# Sheet1.net
KiCad netlist of a schematic drawn in Altium Designer
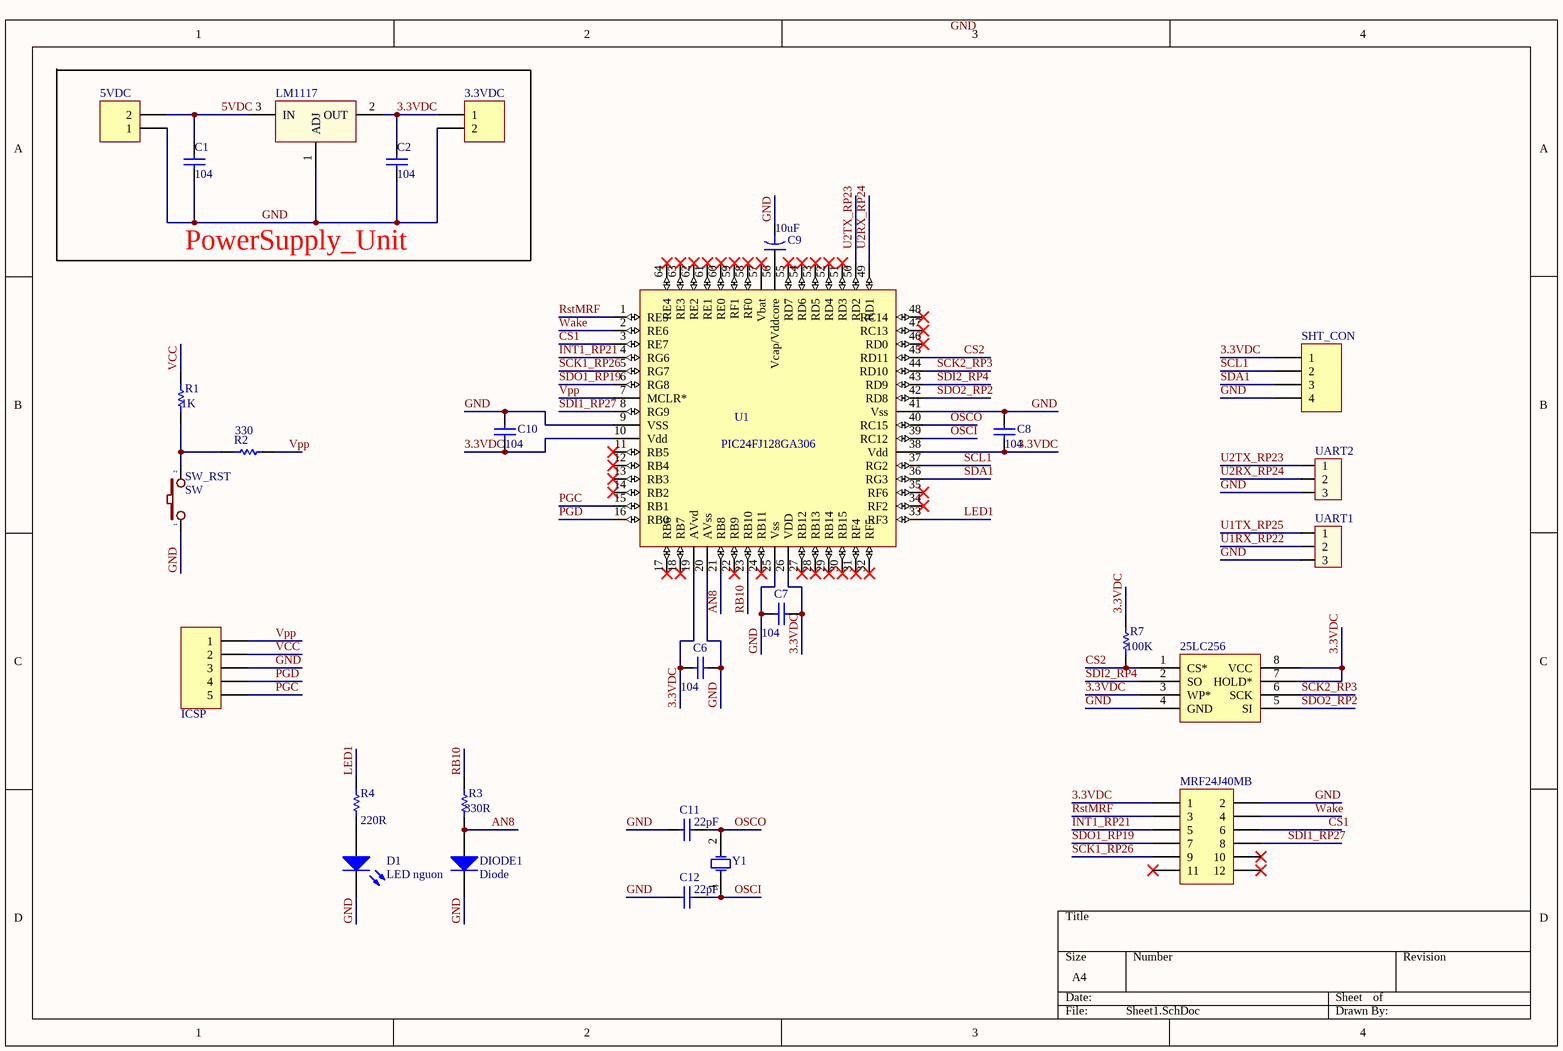
[diagram p0: Sheet1.SchDoc]

(export (version "E")
  (design (tool "Eeschema 10.0.6"))
  (components
    (comp (ref "3.3VDC")
      (value "Header 2")
      (footprint "HDR1X2")
      (description "Header, 2-Pin")
      (fields (field (name "PUBLISHER") "Altium Limited"))
      (libsource (lib "Miscellaneous Connectors") (part "Header 2"))
    )
    (comp (ref "5VDC")
      (value "Header 2")
      (footprint "HDR1X2")
      (description "Header, 2-Pin")
      (fields (field (name "PUBLISHER") "Altium Limited"))
      (libsource (lib "") (part "Header 2_1"))
    )
    (comp (ref "25LC256") (value "25LC256") (footprint "DIP-8") (libsource (lib "25LC256") (part "25LC256")))
    (comp (ref "C1")
      (value "104")
      (footprint "C0805")
      (description "Capacitor")
      (fields (field (name "Comment") "Cap") (field (name "PUBLISHER") "Altium Limited"))
      (libsource (lib "Miscellaneous Devices") (part "Cap"))
    )
    (comp (ref "C2")
      (value "104")
      (footprint "C0805")
      (description "Capacitor")
      (fields (field (name "Comment") "Cap") (field (name "PUBLISHER") "Altium Limited"))
      (libsource (lib "Miscellaneous Devices") (part "Cap"))
    )
    (comp (ref "C6")
      (value "104")
      (footprint "C0805")
      (description "Capacitor")
      (fields (field (name "Comment") "Cap") (field (name "PUBLISHER") "Altium Limited"))
      (libsource (lib "Miscellaneous Devices") (part "Cap"))
    )
    (comp (ref "C7")
      (value "104")
      (footprint "C0805")
      (description "Capacitor")
      (fields (field (name "Comment") "Cap") (field (name "PUBLISHER") "Altium Limited"))
      (libsource (lib "Miscellaneous Devices") (part "Cap"))
    )
    (comp (ref "C8")
      (value "104")
      (footprint "C0805")
      (description "Capacitor")
      (fields (field (name "Comment") "Cap") (field (name "PUBLISHER") "Altium Limited"))
      (libsource (lib "Miscellaneous Devices") (part "Cap"))
    )
    (comp (ref "C9")
      (value "10uF")
      (footprint "CAP P 6.3x5.4")
      (description "Capacitor")
      (fields (field (name "Comment") "Cap2") (field (name "PUBLISHER") "Altium Limited"))
      (libsource (lib "Miscellaneous Devices") (part "Cap2"))
    )
    (comp (ref "C10")
      (value "104")
      (footprint "C0805")
      (description "Capacitor")
      (fields (field (name "Comment") "Cap") (field (name "PUBLISHER") "Altium Limited"))
      (libsource (lib "Miscellaneous Devices") (part "Cap"))
    )
    (comp (ref "C11")
      (value "22pF")
      (footprint "C0805")
      (description "Capacitor")
      (fields (field (name "Comment") "Cap") (field (name "PUBLISHER") "Altium Limited"))
      (libsource (lib "Miscellaneous Devices") (part "Cap"))
    )
    (comp (ref "C12")
      (value "22pF")
      (footprint "C0805")
      (description "Capacitor")
      (fields (field (name "Comment") "Cap") (field (name "PUBLISHER") "Altium Limited"))
      (libsource (lib "Miscellaneous Devices") (part "Cap"))
    )
    (comp (ref "D1")
      (value "LED nguon")
      (footprint "LED3mm")
      (description "Typical INFRARED GaAs LED")
      (fields (field (name "PUBLISHER") "Altium Limited"))
      (libsource (lib "Miscellaneous Devices") (part "LED0"))
    )
    (comp (ref "DIODE1")
      (value "Diode")
      (footprint "DZ0.5A")
      (description "Default Diode")
      (fields (field (name "PUBLISHER") "Altium Limited"))
      (libsource (lib "Miscellaneous Devices") (part "Diode"))
    )
    (comp (ref "ICSP")
      (value "ICSP")
      (footprint "CON5")
      (description "Header, 5-Pin")
      (fields (field (name "PUBLISHER") "Altium Limited"))
      (libsource (lib "Miscellaneous Connectors") (part "Header 5"))
    )
    (comp (ref "LM1117")
      (value "LM317")
      (footprint "SOT223-4N")
      (description "Adj Voltage +1.2 -> +37V")
      (libsource (lib "syhaunguyen") (part "LM317"))
    )
    (comp (ref "MRF24J40MB")
      (value "Header 6X2")
      (footprint "MRF24J40MB_board_mini")
      (description "Header, 6-Pin, Dual row")
      (fields (field (name "PUBLISHER") "Altium Limited"))
      (libsource (lib "Miscellaneous Connectors") (part "Header 6X2"))
    )
    (comp (ref "R1")
      (value "1K")
      (footprint "C0805")
      (description "Resistor")
      (fields (field (name "Comment") "Res1") (field (name "PUBLISHER") "Altium Limited"))
      (libsource (lib "Miscellaneous Devices") (part "Res1"))
    )
    (comp (ref "R2")
      (value "330")
      (footprint "C0805")
      (description "Resistor")
      (fields (field (name "Comment") "res") (field (name "PUBLISHER") "Altium Limited"))
      (libsource (lib "Miscellaneous Devices") (part "Res1"))
    )
    (comp (ref "R3")
      (value "330R")
      (footprint "C0805")
      (description "Resistor")
      (fields (field (name "Comment") "Res1") (field (name "PUBLISHER") "Altium Limited"))
      (libsource (lib "Miscellaneous Devices") (part "Res1"))
    )
    (comp (ref "R4")
      (value "220R")
      (footprint "C0805")
      (description "Resistor")
      (fields (field (name "Comment") "Res1") (field (name "PUBLISHER") "Altium Limited"))
      (libsource (lib "Miscellaneous Devices") (part "Res1"))
    )
    (comp (ref "R7")
      (value "100K")
      (footprint "C0805")
      (description "Semiconductor Resistor")
      (fields (field (name "Comment") "Res Semi") (field (name "PUBLISHER") "Altium Limited"))
      (libsource (lib "Miscellaneous Devices") (part "Res Semi"))
    )
    (comp (ref "SHT_CON")
      (value "SHT10 conector")
      (footprint "CON4")
      (description "Header, 4-Pin")
      (fields (field (name "PUBLISHER") "Altium Limited"))
      (libsource (lib "Miscellaneous Connectors") (part "Header 4"))
    )
    (comp (ref "SW_RST")
      (value "SW")
      (footprint "SW2")
      (description "Switch button 2 pin")
      (libsource (lib "syhaunguyen") (part "SW2"))
    )
    (comp (ref "U1")
      (value "PIC24FJ128GA306")
      (footprint "TQFP-PT64_N")
      (libsource (lib "Mylibbrary") (part "PIC24FJ128GA306"))
    )
    (comp (ref "UART1")
      (value "UART1")
      (footprint "CON3")
      (description "Connector 3")
      (libsource (lib "syhaunguyen") (part "Con3"))
    )
    (comp (ref "UART2")
      (value "UART2")
      (footprint "CON3")
      (description "Connector 3")
      (libsource (lib "syhaunguyen") (part "Con3"))
    )
    (comp (ref "Y1")
      (value "XTAL")
      (footprint "XT2")
      (description "Crystal Oscillator")
      (fields (field (name "PUBLISHER") "Altium Limited"))
      (libsource (lib "Miscellaneous Devices") (part "XTAL"))
    )
  )
  (nets
    (net (code "1") (name "/3.3VDC") (class "Default")
      (node (ref "25LC256") (pin "3") (pinfunction "WP*_3") (pintype "passive"))
      (node (ref "25LC256") (pin "7") (pinfunction "HOLD*_7") (pintype "passive"))
      (node (ref "25LC256") (pin "8") (pinfunction "VCC_8") (pintype "power_in"))
      (node (ref "3.3VDC") (pin "1") (pinfunction "1_1") (pintype "passive"))
      (node (ref "C10") (pin "1") (pinfunction "1_1") (pintype "passive"))
      (node (ref "C2") (pin "2") (pinfunction "2_2") (pintype "passive"))
      (node (ref "C6") (pin "1") (pinfunction "1_1") (pintype "passive"))
      (node (ref "C7") (pin "2") (pinfunction "2_2") (pintype "passive"))
      (node (ref "C8") (pin "1") (pinfunction "1_1") (pintype "passive"))
      (node (ref "LM1117") (pin "2") (pinfunction "OUT_2") (pintype "passive"))
      (node (ref "MRF24J40MB") (pin "1") (pinfunction "1_1") (pintype "passive"))
      (node (ref "R7") (pin "2") (pinfunction "2_2") (pintype "passive"))
      (node (ref "SHT_CON") (pin "1") (pinfunction "1_1") (pintype "passive"))
      (node (ref "U1") (pin "10") (pinfunction "Vdd_10") (pintype "passive"))
      (node (ref "U1") (pin "19") (pinfunction "AVvd_19") (pintype "power_in"))
      (node (ref "U1") (pin "26") (pinfunction "VDD_26") (pintype "power_in"))
      (node (ref "U1") (pin "38") (pinfunction "Vdd_38") (pintype "power_in"))
    )
    (net (code "2") (name "/5VDC") (class "Default")
      (node (ref "5VDC") (pin "2") (pinfunction "2_2") (pintype "passive"))
      (node (ref "C1") (pin "2") (pinfunction "2_2") (pintype "passive"))
      (node (ref "LM1117") (pin "3") (pinfunction "IN_3") (pintype "passive"))
    )
    (net (code "3") (name "/AN8") (class "Default")
      (node (ref "DIODE1") (pin "1") (pinfunction "A_1") (pintype "passive"))
      (node (ref "R3") (pin "1") (pinfunction "1_1") (pintype "passive"))
      (node (ref "U1") (pin "21") (pinfunction "RB8_21") (pintype "bidirectional"))
    )
    (net (code "4") (name "/CS1") (class "Default")
      (node (ref "MRF24J40MB") (pin "6") (pinfunction "6_6") (pintype "passive"))
      (node (ref "U1") (pin "3") (pinfunction "RE7_3") (pintype "bidirectional"))
    )
    (net (code "5") (name "/CS2") (class "Default")
      (node (ref "25LC256") (pin "1") (pinfunction "CS*_1") (pintype "passive"))
      (node (ref "R7") (pin "1") (pinfunction "1_1") (pintype "passive"))
      (node (ref "U1") (pin "45") (pinfunction "RD11_45") (pintype "bidirectional"))
    )
    (net (code "6") (name "/GND") (class "Default")
      (node (ref "25LC256") (pin "4") (pinfunction "GND_4") (pintype "power_in"))
      (node (ref "3.3VDC") (pin "2") (pinfunction "2_2") (pintype "passive"))
      (node (ref "5VDC") (pin "1") (pinfunction "1_1") (pintype "passive"))
      (node (ref "C1") (pin "1") (pinfunction "1_1") (pintype "passive"))
      (node (ref "C10") (pin "2") (pinfunction "2_2") (pintype "passive"))
      (node (ref "C11") (pin "1") (pinfunction "1_1") (pintype "passive"))
      (node (ref "C12") (pin "1") (pinfunction "1_1") (pintype "passive"))
      (node (ref "C2") (pin "1") (pinfunction "1_1") (pintype "passive"))
      (node (ref "C6") (pin "2") (pinfunction "2_2") (pintype "passive"))
      (node (ref "C7") (pin "1") (pinfunction "1_1") (pintype "passive"))
      (node (ref "C8") (pin "2") (pinfunction "2_2") (pintype "passive"))
      (node (ref "C9") (pin "2") (pinfunction "2_2") (pintype "passive"))
      (node (ref "D1") (pin "2") (pinfunction "K_2") (pintype "passive"))
      (node (ref "DIODE1") (pin "2") (pinfunction "K_2") (pintype "passive"))
      (node (ref "ICSP") (pin "3") (pinfunction "3_3") (pintype "passive"))
      (node (ref "LM1117") (pin "1") (pinfunction "ADJ_1") (pintype "passive"))
      (node (ref "MRF24J40MB") (pin "2") (pinfunction "2_2") (pintype "passive"))
      (node (ref "SHT_CON") (pin "4") (pinfunction "4_4") (pintype "passive"))
      (node (ref "SW_RST") (pin "1") (pinfunction "1_1") (pintype "passive"))
      (node (ref "U1") (pin "20") (pinfunction "AVss_20") (pintype "power_in"))
      (node (ref "U1") (pin "25") (pinfunction "Vss_25") (pintype "power_in"))
      (node (ref "U1") (pin "41") (pinfunction "Vss_41") (pintype "power_in"))
      (node (ref "U1") (pin "9") (pinfunction "VSS_9") (pintype "power_in"))
      (node (ref "UART1") (pin "3") (pinfunction "3_3") (pintype "passive"))
      (node (ref "UART2") (pin "3") (pinfunction "3_3") (pintype "passive"))
    )
    (net (code "7") (name "/INT1_RP21") (class "Default")
      (node (ref "MRF24J40MB") (pin "5") (pinfunction "5_5") (pintype "passive"))
      (node (ref "U1") (pin "4") (pinfunction "RG6_4") (pintype "bidirectional"))
    )
    (net (code "8") (name "/LED1") (class "Default")
      (node (ref "R4") (pin "2") (pinfunction "2_2") (pintype "passive"))
      (node (ref "U1") (pin "33") (pinfunction "RF3_33") (pintype "bidirectional"))
    )
    (net (code "9") (name "/OSCI") (class "Default")
      (node (ref "C12") (pin "2") (pinfunction "2_2") (pintype "passive"))
      (node (ref "U1") (pin "39") (pinfunction "RC12_39") (pintype "bidirectional"))
      (node (ref "Y1") (pin "1") (pinfunction "OSC1_1") (pintype "passive"))
    )
    (net (code "10") (name "/OSCO") (class "Default")
      (node (ref "C11") (pin "2") (pinfunction "2_2") (pintype "passive"))
      (node (ref "U1") (pin "40") (pinfunction "RC15_40") (pintype "bidirectional"))
      (node (ref "Y1") (pin "2") (pinfunction "OSC2_2") (pintype "passive"))
    )
    (net (code "11") (name "/PGC") (class "Default")
      (node (ref "ICSP") (pin "5") (pinfunction "5_5") (pintype "passive"))
      (node (ref "U1") (pin "15") (pinfunction "RB1_15") (pintype "bidirectional"))
    )
    (net (code "12") (name "/PGD") (class "Default")
      (node (ref "ICSP") (pin "4") (pinfunction "4_4") (pintype "passive"))
      (node (ref "U1") (pin "16") (pinfunction "RB0_16") (pintype "bidirectional"))
    )
    (net (code "13") (name "/RB10") (class "Default")
      (node (ref "R3") (pin "2") (pinfunction "2_2") (pintype "passive"))
      (node (ref "U1") (pin "23") (pinfunction "RB10_23") (pintype "bidirectional"))
    )
    (net (code "14") (name "/RstMRF") (class "Default")
      (node (ref "MRF24J40MB") (pin "3") (pinfunction "3_3") (pintype "passive"))
      (node (ref "U1") (pin "1") (pinfunction "RE5_1") (pintype "bidirectional"))
    )
    (net (code "15") (name "/SCK1_RP26") (class "Default")
      (node (ref "MRF24J40MB") (pin "9") (pinfunction "9_9") (pintype "passive"))
      (node (ref "U1") (pin "5") (pinfunction "RG7_5") (pintype "bidirectional"))
    )
    (net (code "16") (name "/SCK2_RP3") (class "Default")
      (node (ref "25LC256") (pin "6") (pinfunction "SCK_6") (pintype "passive"))
      (node (ref "U1") (pin "44") (pinfunction "RD10_44") (pintype "bidirectional"))
    )
    (net (code "17") (name "/SCL1") (class "Default")
      (node (ref "SHT_CON") (pin "2") (pinfunction "2_2") (pintype "passive"))
      (node (ref "U1") (pin "37") (pinfunction "RG2_37") (pintype "bidirectional"))
    )
    (net (code "18") (name "/SDA1") (class "Default")
      (node (ref "SHT_CON") (pin "3") (pinfunction "3_3") (pintype "passive"))
      (node (ref "U1") (pin "36") (pinfunction "RG3_36") (pintype "bidirectional"))
    )
    (net (code "19") (name "/SDI1_RP27") (class "Default")
      (node (ref "MRF24J40MB") (pin "8") (pinfunction "8_8") (pintype "passive"))
      (node (ref "U1") (pin "8") (pinfunction "RG9_8") (pintype "bidirectional"))
    )
    (net (code "20") (name "/SDI2_RP4") (class "Default")
      (node (ref "25LC256") (pin "2") (pinfunction "SO_2") (pintype "passive"))
      (node (ref "U1") (pin "43") (pinfunction "RD9_43") (pintype "bidirectional"))
    )
    (net (code "21") (name "/SDO1_RP19") (class "Default")
      (node (ref "MRF24J40MB") (pin "7") (pinfunction "7_7") (pintype "passive"))
      (node (ref "U1") (pin "6") (pinfunction "RG8_6") (pintype "bidirectional"))
    )
    (net (code "22") (name "/SDO2_RP2") (class "Default")
      (node (ref "25LC256") (pin "5") (pinfunction "SI_5") (pintype "passive"))
      (node (ref "U1") (pin "42") (pinfunction "RD8_42") (pintype "bidirectional"))
    )
    (net (code "23") (name "/U1RX_RP22") (class "Default")
      (node (ref "UART1") (pin "2") (pinfunction "2_2") (pintype "passive"))
    )
    (net (code "24") (name "/U1TX_RP25") (class "Default")
      (node (ref "UART1") (pin "1") (pinfunction "1_1") (pintype "passive"))
    )
    (net (code "25") (name "/U2RX_RP24") (class "Default")
      (node (ref "U1") (pin "49") (pinfunction "RD1_49") (pintype "bidirectional"))
      (node (ref "UART2") (pin "2") (pinfunction "2_2") (pintype "passive"))
    )
    (net (code "26") (name "/U2TX_RP23") (class "Default")
      (node (ref "U1") (pin "50") (pinfunction "RD2_50") (pintype "bidirectional"))
      (node (ref "UART2") (pin "1") (pinfunction "1_1") (pintype "passive"))
    )
    (net (code "27") (name "/VCC") (class "Default")
      (node (ref "ICSP") (pin "2") (pinfunction "2_2") (pintype "passive"))
      (node (ref "R1") (pin "2") (pinfunction "2_2") (pintype "passive"))
    )
    (net (code "28") (name "/Vpp") (class "Default")
      (node (ref "ICSP") (pin "1") (pinfunction "1_1") (pintype "passive"))
      (node (ref "R2") (pin "2") (pinfunction "2_2") (pintype "passive"))
      (node (ref "U1") (pin "7") (pinfunction "MCLR*_7") (pintype "passive"))
    )
    (net (code "29") (name "/Wake") (class "Default")
      (node (ref "MRF24J40MB") (pin "4") (pinfunction "4_4") (pintype "passive"))
      (node (ref "U1") (pin "2") (pinfunction "RE6_2") (pintype "bidirectional"))
    )
    (net (code "30") (name "Net-(D1-A)") (class "Default")
      (node (ref "D1") (pin "1") (pinfunction "A_1") (pintype "passive"))
      (node (ref "R4") (pin "1") (pinfunction "1_1") (pintype "passive"))
    )
    (net (code "31") (name "Net-(R1-Pad1)") (class "Default")
      (node (ref "R1") (pin "1") (pinfunction "1_1") (pintype "passive"))
      (node (ref "R2") (pin "1") (pinfunction "1_1") (pintype "passive"))
      (node (ref "SW_RST") (pin "2") (pinfunction "2_2") (pintype "passive"))
    )
    (net (code "32") (name "Net-(U1-Vcap{slash}Vddcore)") (class "Default")
      (node (ref "C9") (pin "1") (pinfunction "1_1") (pintype "passive"))
      (node (ref "U1") (pin "56") (pinfunction "Vcap/Vddcore_56") (pintype "power_in"))
    )
    (net (code "33") (name "unconnected-(MRF24J40MB-Pad10)") (class "Default")
      (node (ref "MRF24J40MB") (pin "10") (pinfunction "10_10") (pintype "passive+no_connect"))
    )
    (net (code "34") (name "unconnected-(MRF24J40MB-Pad11)") (class "Default")
      (node (ref "MRF24J40MB") (pin "11") (pinfunction "11_11") (pintype "passive+no_connect"))
    )
    (net (code "35") (name "unconnected-(MRF24J40MB-Pad12)") (class "Default")
      (node (ref "MRF24J40MB") (pin "12") (pinfunction "12_12") (pintype "passive+no_connect"))
    )
    (net (code "36") (name "unconnected-(U1-RB2-Pad14)") (class "Default")
      (node (ref "U1") (pin "14") (pinfunction "RB2_14") (pintype "bidirectional+no_connect"))
    )
    (net (code "37") (name "unconnected-(U1-RB3-Pad13)") (class "Default")
      (node (ref "U1") (pin "13") (pinfunction "RB3_13") (pintype "bidirectional+no_connect"))
    )
    (net (code "38") (name "unconnected-(U1-RB4-Pad12)") (class "Default")
      (node (ref "U1") (pin "12") (pinfunction "RB4_12") (pintype "bidirectional+no_connect"))
    )
    (net (code "39") (name "unconnected-(U1-RB5-Pad11)") (class "Default")
      (node (ref "U1") (pin "11") (pinfunction "RB5_11") (pintype "bidirectional+no_connect"))
    )
    (net (code "40") (name "unconnected-(U1-RB6-Pad17)") (class "Default")
      (node (ref "U1") (pin "17") (pinfunction "RB6_17") (pintype "bidirectional+no_connect"))
    )
    (net (code "41") (name "unconnected-(U1-RB7-Pad18)") (class "Default")
      (node (ref "U1") (pin "18") (pinfunction "RB7_18") (pintype "bidirectional+no_connect"))
    )
    (net (code "42") (name "unconnected-(U1-RB9-Pad22)") (class "Default")
      (node (ref "U1") (pin "22") (pinfunction "RB9_22") (pintype "bidirectional+no_connect"))
    )
    (net (code "43") (name "unconnected-(U1-RB11-Pad24)") (class "Default")
      (node (ref "U1") (pin "24") (pinfunction "RB11_24") (pintype "bidirectional+no_connect"))
    )
    (net (code "44") (name "unconnected-(U1-RB12-Pad27)") (class "Default")
      (node (ref "U1") (pin "27") (pinfunction "RB12_27") (pintype "bidirectional+no_connect"))
    )
    (net (code "45") (name "unconnected-(U1-RB13-Pad28)") (class "Default")
      (node (ref "U1") (pin "28") (pinfunction "RB13_28") (pintype "bidirectional+no_connect"))
    )
    (net (code "46") (name "unconnected-(U1-RB14-Pad29)") (class "Default")
      (node (ref "U1") (pin "29") (pinfunction "RB14_29") (pintype "bidirectional+no_connect"))
    )
    (net (code "47") (name "unconnected-(U1-RB15-Pad30)") (class "Default")
      (node (ref "U1") (pin "30") (pinfunction "RB15_30") (pintype "bidirectional+no_connect"))
    )
    (net (code "48") (name "unconnected-(U1-RC13-Pad47)") (class "Default")
      (node (ref "U1") (pin "47") (pinfunction "RC13_47") (pintype "bidirectional+no_connect"))
    )
    (net (code "49") (name "unconnected-(U1-RC14-Pad48)") (class "Default")
      (node (ref "U1") (pin "48") (pinfunction "RC14_48") (pintype "bidirectional+no_connect"))
    )
    (net (code "50") (name "unconnected-(U1-RD0-Pad46)") (class "Default")
      (node (ref "U1") (pin "46") (pinfunction "RD0_46") (pintype "bidirectional+no_connect"))
    )
    (net (code "51") (name "unconnected-(U1-RD3-Pad51)") (class "Default")
      (node (ref "U1") (pin "51") (pinfunction "RD3_51") (pintype "bidirectional+no_connect"))
    )
    (net (code "52") (name "unconnected-(U1-RD4-Pad52)") (class "Default")
      (node (ref "U1") (pin "52") (pinfunction "RD4_52") (pintype "bidirectional+no_connect"))
    )
    (net (code "53") (name "unconnected-(U1-RD5-Pad53)") (class "Default")
      (node (ref "U1") (pin "53") (pinfunction "RD5_53") (pintype "bidirectional+no_connect"))
    )
    (net (code "54") (name "unconnected-(U1-RD6-Pad54)") (class "Default")
      (node (ref "U1") (pin "54") (pinfunction "RD6_54") (pintype "bidirectional+no_connect"))
    )
    (net (code "55") (name "unconnected-(U1-RD7-Pad55)") (class "Default")
      (node (ref "U1") (pin "55") (pinfunction "RD7_55") (pintype "bidirectional+no_connect"))
    )
    (net (code "56") (name "unconnected-(U1-RE0-Pad60)") (class "Default")
      (node (ref "U1") (pin "60") (pinfunction "RE0_60") (pintype "bidirectional+no_connect"))
    )
    (net (code "57") (name "unconnected-(U1-RE1-Pad61)") (class "Default")
      (node (ref "U1") (pin "61") (pinfunction "RE1_61") (pintype "bidirectional+no_connect"))
    )
    (net (code "58") (name "unconnected-(U1-RE2-Pad62)") (class "Default")
      (node (ref "U1") (pin "62") (pinfunction "RE2_62") (pintype "bidirectional+no_connect"))
    )
    (net (code "59") (name "unconnected-(U1-RE3-Pad63)") (class "Default")
      (node (ref "U1") (pin "63") (pinfunction "RE3_63") (pintype "bidirectional+no_connect"))
    )
    (net (code "60") (name "unconnected-(U1-RE4-Pad64)") (class "Default")
      (node (ref "U1") (pin "64") (pinfunction "RE4_64") (pintype "bidirectional+no_connect"))
    )
    (net (code "61") (name "unconnected-(U1-RF0-Pad58)") (class "Default")
      (node (ref "U1") (pin "58") (pinfunction "RF0_58") (pintype "bidirectional+no_connect"))
    )
    (net (code "62") (name "unconnected-(U1-RF1-Pad59)") (class "Default")
      (node (ref "U1") (pin "59") (pinfunction "RF1_59") (pintype "bidirectional+no_connect"))
    )
    (net (code "63") (name "unconnected-(U1-RF2-Pad34)") (class "Default")
      (node (ref "U1") (pin "34") (pinfunction "RF2_34") (pintype "bidirectional+no_connect"))
    )
    (net (code "64") (name "unconnected-(U1-RF4-Pad31)") (class "Default")
      (node (ref "U1") (pin "31") (pinfunction "RF4_31") (pintype "bidirectional+no_connect"))
    )
    (net (code "65") (name "unconnected-(U1-RF5-Pad32)") (class "Default")
      (node (ref "U1") (pin "32") (pinfunction "RF5_32") (pintype "bidirectional+no_connect"))
    )
    (net (code "66") (name "unconnected-(U1-RF6-Pad35)") (class "Default")
      (node (ref "U1") (pin "35") (pinfunction "RF6_35") (pintype "bidirectional+no_connect"))
    )
    (net (code "67") (name "unconnected-(U1-Vbat-Pad57)") (class "Default")
      (node (ref "U1") (pin "57") (pinfunction "Vbat_57") (pintype "power_in+no_connect"))
    )
  )
)
